# tb-batt-6s.net
KiCad netlist of a schematic drawn in Altium Designer
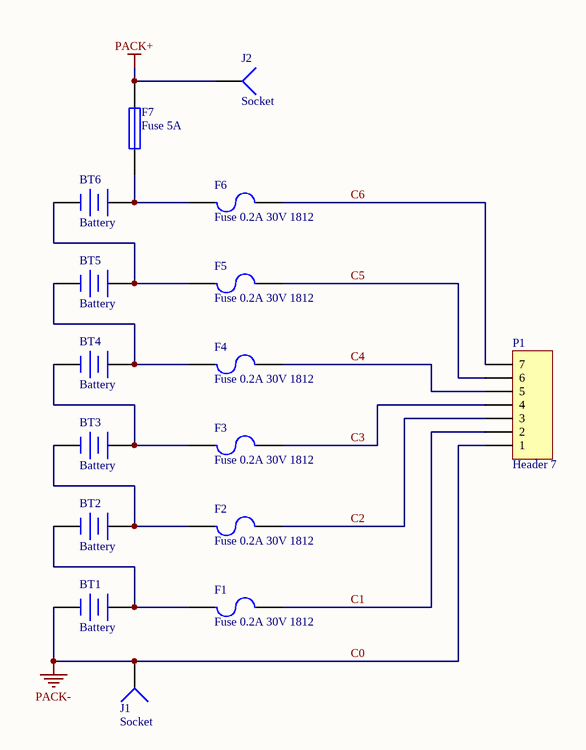
[diagram p0: tb-batt-6s.SchDoc]

(export (version "E")
  (design (tool "Eeschema 10.0.6"))
  (components
    (comp (ref "BT1")
      (value "Battery")
      (footprint "BAT-2")
      (description "Multicell Battery")
      (fields (field (name "PUBLISHER") "Altium Limited"))
      (libsource (lib "Miscellaneous Devices") (part "Battery"))
    )
    (comp (ref "BT2")
      (value "Battery")
      (footprint "BAT-2")
      (description "Multicell Battery")
      (fields (field (name "PUBLISHER") "Altium Limited"))
      (libsource (lib "Miscellaneous Devices") (part "Battery"))
    )
    (comp (ref "BT3")
      (value "Battery")
      (footprint "BAT-2")
      (description "Multicell Battery")
      (fields (field (name "PUBLISHER") "Altium Limited"))
      (libsource (lib "Miscellaneous Devices") (part "Battery"))
    )
    (comp (ref "BT4")
      (value "Battery")
      (footprint "BAT-2")
      (description "Multicell Battery")
      (fields (field (name "PUBLISHER") "Altium Limited"))
      (libsource (lib "Miscellaneous Devices") (part "Battery"))
    )
    (comp (ref "BT5")
      (value "Battery")
      (footprint "BAT-2")
      (description "Multicell Battery")
      (fields (field (name "PUBLISHER") "Altium Limited"))
      (libsource (lib "Miscellaneous Devices") (part "Battery"))
    )
    (comp (ref "BT6")
      (value "Battery")
      (footprint "BAT-2")
      (description "Multicell Battery")
      (fields (field (name "PUBLISHER") "Altium Limited"))
      (libsource (lib "Miscellaneous Devices") (part "Battery"))
    )
    (comp (ref "F1")
      (value "Fuse 0.2A 30V 1812")
      (footprint "1812")
      (description "Fuse")
      (fields (field (name "PUBLISHER") "Altium Limited"))
      (libsource (lib "Miscellaneous Devices") (part "Fuse 2"))
    )
    (comp (ref "F2")
      (value "Fuse 0.2A 30V 1812")
      (footprint "1812")
      (description "Fuse")
      (fields (field (name "PUBLISHER") "Altium Limited"))
      (libsource (lib "Miscellaneous Devices") (part "Fuse 2"))
    )
    (comp (ref "F3")
      (value "Fuse 0.2A 30V 1812")
      (footprint "1812")
      (description "Fuse")
      (fields (field (name "PUBLISHER") "Altium Limited"))
      (libsource (lib "Miscellaneous Devices") (part "Fuse 2"))
    )
    (comp (ref "F4")
      (value "Fuse 0.2A 30V 1812")
      (footprint "1812")
      (description "Fuse")
      (fields (field (name "PUBLISHER") "Altium Limited"))
      (libsource (lib "Miscellaneous Devices") (part "Fuse 2"))
    )
    (comp (ref "F5")
      (value "Fuse 0.2A 30V 1812")
      (footprint "1812")
      (description "Fuse")
      (fields (field (name "PUBLISHER") "Altium Limited"))
      (libsource (lib "Miscellaneous Devices") (part "Fuse 2"))
    )
    (comp (ref "F6")
      (value "Fuse 0.2A 30V 1812")
      (footprint "1812")
      (description "Fuse")
      (fields (field (name "PUBLISHER") "Altium Limited"))
      (libsource (lib "Miscellaneous Devices") (part "Fuse 2"))
    )
    (comp (ref "F7")
      (value "Fuse 5A")
      (footprint "PIN-W2/E2.8")
      (description "Fuse")
      (fields (field (name "PUBLISHER") "Altium Limited"))
      (libsource (lib "Miscellaneous Devices") (part "Fuse 1"))
    )
    (comp (ref "J1")
      (value "Socket")
      (fields (field (name "PUBLISHER") "Altium Limited"))
      (libsource (lib "Miscellaneous Connectors") (part "Socket"))
    )
    (comp (ref "J2")
      (value "Socket")
      (fields (field (name "PUBLISHER") "Altium Limited"))
      (libsource (lib "Miscellaneous Connectors") (part "Socket"))
    )
    (comp (ref "P1")
      (value "Header 7")
      (footprint "HDR1X7")
      (description "Header, 7-Pin")
      (fields (field (name "PUBLISHER") "Altium Limited"))
      (libsource (lib "Miscellaneous Connectors") (part "Header 7"))
    )
  )
  (nets
    (net (code "1") (name "/C1") (class "Default")
      (node (ref "F1") (pin "2") (pinfunction "2_2") (pintype "passive"))
      (node (ref "P1") (pin "2") (pinfunction "2_2") (pintype "passive"))
    )
    (net (code "2") (name "/C2") (class "Default")
      (node (ref "F2") (pin "2") (pinfunction "2_2") (pintype "passive"))
      (node (ref "P1") (pin "3") (pinfunction "3_3") (pintype "passive"))
    )
    (net (code "3") (name "/C3") (class "Default")
      (node (ref "F3") (pin "2") (pinfunction "2_2") (pintype "passive"))
      (node (ref "P1") (pin "4") (pinfunction "4_4") (pintype "passive"))
    )
    (net (code "4") (name "/C4") (class "Default")
      (node (ref "F4") (pin "2") (pinfunction "2_2") (pintype "passive"))
      (node (ref "P1") (pin "5") (pinfunction "5_5") (pintype "passive"))
    )
    (net (code "5") (name "/C5") (class "Default")
      (node (ref "F5") (pin "2") (pinfunction "2_2") (pintype "passive"))
      (node (ref "P1") (pin "6") (pinfunction "6_6") (pintype "passive"))
    )
    (net (code "6") (name "/C6") (class "Default")
      (node (ref "F6") (pin "2") (pinfunction "2_2") (pintype "passive"))
      (node (ref "P1") (pin "7") (pinfunction "7_7") (pintype "passive"))
    )
    (net (code "7") (name "Net-(BT1-+)") (class "Default")
      (node (ref "BT1") (pin "1") (pinfunction "+_1") (pintype "passive"))
      (node (ref "BT2") (pin "2") (pinfunction "-_2") (pintype "passive"))
      (node (ref "F1") (pin "1") (pinfunction "1_1") (pintype "passive"))
    )
    (net (code "8") (name "Net-(BT2-+)") (class "Default")
      (node (ref "BT2") (pin "1") (pinfunction "+_1") (pintype "passive"))
      (node (ref "BT3") (pin "2") (pinfunction "-_2") (pintype "passive"))
      (node (ref "F2") (pin "1") (pinfunction "1_1") (pintype "passive"))
    )
    (net (code "9") (name "Net-(BT3-+)") (class "Default")
      (node (ref "BT3") (pin "1") (pinfunction "+_1") (pintype "passive"))
      (node (ref "BT4") (pin "2") (pinfunction "-_2") (pintype "passive"))
      (node (ref "F3") (pin "1") (pinfunction "1_1") (pintype "passive"))
    )
    (net (code "10") (name "Net-(BT4-+)") (class "Default")
      (node (ref "BT4") (pin "1") (pinfunction "+_1") (pintype "passive"))
      (node (ref "BT5") (pin "2") (pinfunction "-_2") (pintype "passive"))
      (node (ref "F4") (pin "1") (pinfunction "1_1") (pintype "passive"))
    )
    (net (code "11") (name "Net-(BT5-+)") (class "Default")
      (node (ref "BT5") (pin "1") (pinfunction "+_1") (pintype "passive"))
      (node (ref "BT6") (pin "2") (pinfunction "-_2") (pintype "passive"))
      (node (ref "F5") (pin "1") (pinfunction "1_1") (pintype "passive"))
    )
    (net (code "12") (name "Net-(BT6-+)") (class "Default")
      (node (ref "BT6") (pin "1") (pinfunction "+_1") (pintype "passive"))
      (node (ref "F6") (pin "1") (pinfunction "1_1") (pintype "passive"))
      (node (ref "F7") (pin "1") (pinfunction "1_1") (pintype "passive"))
    )
    (net (code "13") (name "PACK+") (class "Default")
      (node (ref "F7") (pin "2") (pinfunction "2_2") (pintype "passive"))
      (node (ref "J2") (pin "1") (pinfunction "1_1") (pintype "passive"))
    )
    (net (code "14") (name "PACK-") (class "Default")
      (node (ref "BT1") (pin "2") (pinfunction "-_2") (pintype "passive"))
      (node (ref "J1") (pin "1") (pinfunction "1_1") (pintype "passive"))
      (node (ref "P1") (pin "1") (pinfunction "1_1") (pintype "passive"))
    )
  )
)
